# Tp_integrador-Perifericos.net
KiCad netlist of a schematic drawn in Altium Designer
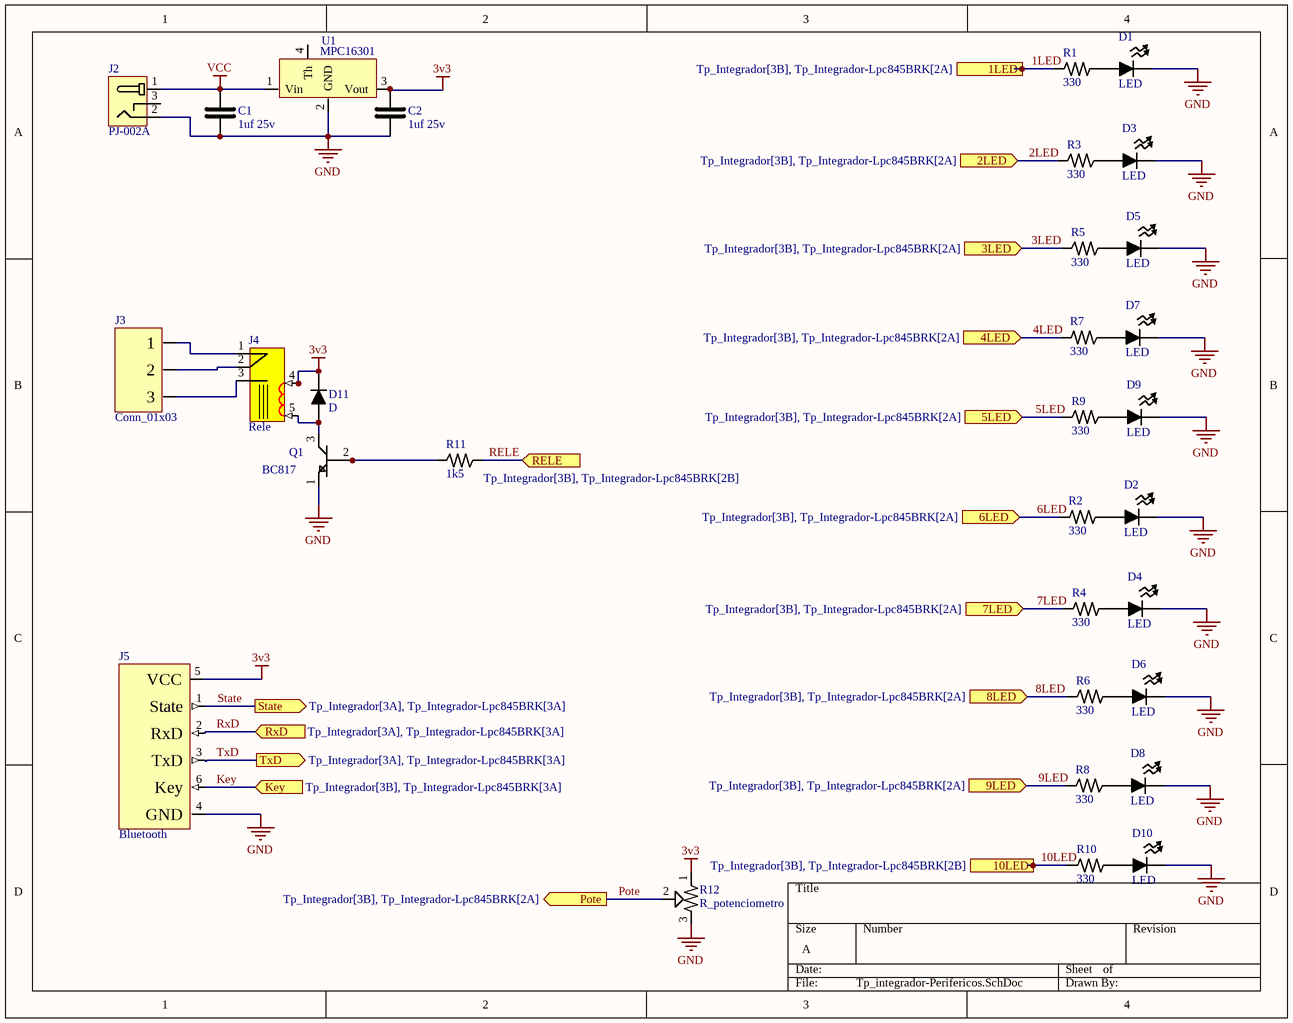
[diagram p0: Tp_integrador-Perifericos.SchDoc]

(export (version "E")
  (design (tool "Eeschema 10.0.6"))
  (components
    (comp (ref "C1")
      (value "1uf 25v")
      (footprint "C_0805")
      (description "Capacitor NP")
      (libsource (lib "Tp_Integrador-SchLib") (part "Capacitor Non Polarized_1"))
    )
    (comp (ref "C2")
      (value "1uf 25v")
      (footprint "C_0805")
      (description "Capacitor NP")
      (libsource (lib "Tp_Integrador-SchLib") (part "Capacitor Non Polarized_1"))
    )
    (comp (ref "D1")
      (value "LED")
      (footprint "LED 5MM")
      (description "Led")
      (libsource (lib "Tp_Integrador-SchLib") (part "LED"))
    )
    (comp (ref "D2")
      (value "LED")
      (footprint "LED 5MM")
      (description "Led")
      (libsource (lib "Tp_Integrador-SchLib") (part "LED"))
    )
    (comp (ref "D3")
      (value "LED")
      (footprint "LED 5MM")
      (description "Led")
      (libsource (lib "Tp_Integrador-SchLib") (part "LED"))
    )
    (comp (ref "D4")
      (value "LED")
      (footprint "LED 5MM")
      (description "Led")
      (libsource (lib "Tp_Integrador-SchLib") (part "LED"))
    )
    (comp (ref "D5")
      (value "LED")
      (footprint "LED 5MM")
      (description "Led")
      (libsource (lib "Tp_Integrador-SchLib") (part "LED"))
    )
    (comp (ref "D6")
      (value "LED")
      (footprint "LED 5MM")
      (description "Led")
      (libsource (lib "Tp_Integrador-SchLib") (part "LED"))
    )
    (comp (ref "D7")
      (value "LED")
      (footprint "LED 5MM")
      (description "Led")
      (libsource (lib "Tp_Integrador-SchLib") (part "LED"))
    )
    (comp (ref "D8")
      (value "LED")
      (footprint "LED 5MM")
      (description "Led")
      (libsource (lib "Tp_Integrador-SchLib") (part "LED"))
    )
    (comp (ref "D9")
      (value "LED")
      (footprint "LED 5MM")
      (description "Led")
      (libsource (lib "Tp_Integrador-SchLib") (part "LED"))
    )
    (comp (ref "D10")
      (value "LED")
      (footprint "LED 5MM")
      (description "Led")
      (libsource (lib "Tp_Integrador-SchLib") (part "LED"))
    )
    (comp (ref "D11")
      (value "D")
      (footprint "Diode")
      (description "DIODO")
      (libsource (lib "Tp_Integrador-SchLib") (part "D"))
    )
    (comp (ref "J2")
      (value "PJ-002A")
      (footprint "Jack")
      (libsource (lib "Tp_Integrador-SchLib") (part "PJ-002A"))
    )
    (comp (ref "J3")
      (value "Conn_01x03")
      (footprint "Bornier")
      (description "Header 3x1")
      (libsource (lib "Tp_Integrador-SchLib") (part "Conn_01x03"))
    )
    (comp (ref "J4") (value "Rele") (footprint "rele") (libsource (lib "Tp_Integrador-SchLib") (part "Rele")))
    (comp (ref "J5")
      (value "Bluetooth")
      (footprint "Hc-05")
      (description "Header 6x1")
      (libsource (lib "Tp_Integrador-SchLib") (part "Bluetooth"))
    )
    (comp (ref "Q1")
      (value "BC817")
      (footprint "Transistor")
      (description "Transistor NPN")
      (libsource (lib "Tp_Integrador-SchLib") (part "Transistor NPN"))
    )
    (comp (ref "R1")
      (value "330")
      (footprint "R_0805")
      (description "Resistor")
      (libsource (lib "Tp_Integrador-SchLib") (part "Resistor"))
    )
    (comp (ref "R2")
      (value "330")
      (footprint "R_0805")
      (description "Resistor")
      (libsource (lib "Tp_Integrador-SchLib") (part "Resistor"))
    )
    (comp (ref "R3")
      (value "330")
      (footprint "R_0805")
      (description "Resistor")
      (libsource (lib "Tp_Integrador-SchLib") (part "Resistor"))
    )
    (comp (ref "R4")
      (value "330")
      (footprint "R_0805")
      (description "Resistor")
      (libsource (lib "Tp_Integrador-SchLib") (part "Resistor"))
    )
    (comp (ref "R5")
      (value "330")
      (footprint "R_0805")
      (description "Resistor")
      (libsource (lib "Tp_Integrador-SchLib") (part "Resistor"))
    )
    (comp (ref "R6")
      (value "330")
      (footprint "R_0805")
      (description "Resistor")
      (libsource (lib "Tp_Integrador-SchLib") (part "Resistor"))
    )
    (comp (ref "R7")
      (value "330")
      (footprint "R_0805")
      (description "Resistor")
      (libsource (lib "Tp_Integrador-SchLib") (part "Resistor"))
    )
    (comp (ref "R8")
      (value "330")
      (footprint "R_0805")
      (description "Resistor")
      (libsource (lib "Tp_Integrador-SchLib") (part "Resistor"))
    )
    (comp (ref "R9")
      (value "330")
      (footprint "R_0805")
      (description "Resistor")
      (libsource (lib "Tp_Integrador-SchLib") (part "Resistor"))
    )
    (comp (ref "R10")
      (value "330")
      (footprint "R_0805")
      (description "Resistor")
      (libsource (lib "Tp_Integrador-SchLib") (part "Resistor"))
    )
    (comp (ref "R11")
      (value "1k5")
      (footprint "R_0805")
      (description "Resistor")
      (libsource (lib "Tp_Integrador-SchLib") (part "Resistor"))
    )
    (comp (ref "R12")
      (value "R_potenciometro")
      (footprint "POTE_9.5MM_PTV09-horizontal")
      (libsource (lib "Tp_Integrador-SchLib") (part "R_potenciometro"))
    )
    (comp (ref "U1")
      (value "MPC16301")
      (footprint "Regulador")
      (description "Regulador Lineal")
      (libsource (lib "Tp_Integrador-SchLib") (part "MPC16301"))
    )
  )
  (nets
    (net (code "1") (name "/1LED") (class "Default")
      (node (ref "R1") (pin "2") (pinfunction "2_2") (pintype "passive"))
    )
    (net (code "2") (name "/2LED") (class "Default")
      (node (ref "R3") (pin "2") (pinfunction "2_2") (pintype "passive"))
    )
    (net (code "3") (name "/3LED") (class "Default")
      (node (ref "R5") (pin "2") (pinfunction "2_2") (pintype "passive"))
    )
    (net (code "4") (name "/4LED") (class "Default")
      (node (ref "R7") (pin "2") (pinfunction "2_2") (pintype "passive"))
    )
    (net (code "5") (name "/5LED") (class "Default")
      (node (ref "R9") (pin "2") (pinfunction "2_2") (pintype "passive"))
    )
    (net (code "6") (name "/6LED") (class "Default")
      (node (ref "R2") (pin "2") (pinfunction "2_2") (pintype "passive"))
    )
    (net (code "7") (name "/7LED") (class "Default")
      (node (ref "R4") (pin "2") (pinfunction "2_2") (pintype "passive"))
    )
    (net (code "8") (name "/8LED") (class "Default")
      (node (ref "R6") (pin "2") (pinfunction "2_2") (pintype "passive"))
    )
    (net (code "9") (name "/9LED") (class "Default")
      (node (ref "R8") (pin "2") (pinfunction "2_2") (pintype "passive"))
    )
    (net (code "10") (name "/10LED") (class "Default")
      (node (ref "R10") (pin "2") (pinfunction "2_2") (pintype "passive"))
    )
    (net (code "11") (name "/Key") (class "Default")
      (node (ref "J5") (pin "6") (pinfunction "Key_6") (pintype "input"))
    )
    (net (code "12") (name "/Pote") (class "Default")
      (node (ref "R12") (pin "2") (pinfunction "2_2") (pintype "passive"))
    )
    (net (code "13") (name "/RELE") (class "Default")
      (node (ref "R11") (pin "1") (pinfunction "1_1") (pintype "passive"))
    )
    (net (code "14") (name "/RxD") (class "Default")
      (node (ref "J5") (pin "2") (pinfunction "RxD_2") (pintype "input"))
    )
    (net (code "15") (name "/State") (class "Default")
      (node (ref "J5") (pin "1") (pinfunction "State_1") (pintype "output"))
    )
    (net (code "16") (name "/TxD") (class "Default")
      (node (ref "J5") (pin "3") (pinfunction "TxD_3") (pintype "output"))
    )
    (net (code "17") (name "3v3") (class "Default")
      (node (ref "C2") (pin "1") (pinfunction "1_1") (pintype "passive"))
      (node (ref "D11") (pin "2") (pinfunction "K_2") (pintype "passive"))
      (node (ref "J4") (pin "4") (pinfunction "4_4") (pintype "input"))
      (node (ref "J5") (pin "5") (pinfunction "VCC_5") (pintype "power_in"))
      (node (ref "R12") (pin "1") (pinfunction "1_1") (pintype "passive"))
      (node (ref "U1") (pin "3") (pinfunction "Vout_3") (pintype "passive"))
    )
    (net (code "18") (name "GND") (class "Default")
      (node (ref "C1") (pin "2") (pinfunction "2_2") (pintype "passive"))
      (node (ref "C2") (pin "2") (pinfunction "2_2") (pintype "passive"))
      (node (ref "D1") (pin "2") (pinfunction "K_2") (pintype "passive"))
      (node (ref "D10") (pin "2") (pinfunction "K_2") (pintype "passive"))
      (node (ref "D2") (pin "2") (pinfunction "K_2") (pintype "passive"))
      (node (ref "D3") (pin "2") (pinfunction "K_2") (pintype "passive"))
      (node (ref "D4") (pin "2") (pinfunction "K_2") (pintype "passive"))
      (node (ref "D5") (pin "2") (pinfunction "K_2") (pintype "passive"))
      (node (ref "D6") (pin "2") (pinfunction "K_2") (pintype "passive"))
      (node (ref "D7") (pin "2") (pinfunction "K_2") (pintype "passive"))
      (node (ref "D8") (pin "2") (pinfunction "K_2") (pintype "passive"))
      (node (ref "D9") (pin "2") (pinfunction "K_2") (pintype "passive"))
      (node (ref "J2") (pin "2") (pinfunction "2_2") (pintype "passive"))
      (node (ref "J5") (pin "4") (pinfunction "GND_4") (pintype "power_in"))
      (node (ref "Q1") (pin "1") (pinfunction "1_1") (pintype "passive"))
      (node (ref "R12") (pin "3") (pinfunction "3_3") (pintype "passive"))
      (node (ref "U1") (pin "2") (pinfunction "GND_2") (pintype "passive"))
    )
    (net (code "19") (name "Net-(D1-A)") (class "Default")
      (node (ref "D1") (pin "1") (pinfunction "A_1") (pintype "passive"))
      (node (ref "R1") (pin "1") (pinfunction "1_1") (pintype "passive"))
    )
    (net (code "20") (name "Net-(D2-A)") (class "Default")
      (node (ref "D2") (pin "1") (pinfunction "A_1") (pintype "passive"))
      (node (ref "R2") (pin "1") (pinfunction "1_1") (pintype "passive"))
    )
    (net (code "21") (name "Net-(D3-A)") (class "Default")
      (node (ref "D3") (pin "1") (pinfunction "A_1") (pintype "passive"))
      (node (ref "R3") (pin "1") (pinfunction "1_1") (pintype "passive"))
    )
    (net (code "22") (name "Net-(D4-A)") (class "Default")
      (node (ref "D4") (pin "1") (pinfunction "A_1") (pintype "passive"))
      (node (ref "R4") (pin "1") (pinfunction "1_1") (pintype "passive"))
    )
    (net (code "23") (name "Net-(D5-A)") (class "Default")
      (node (ref "D5") (pin "1") (pinfunction "A_1") (pintype "passive"))
      (node (ref "R5") (pin "1") (pinfunction "1_1") (pintype "passive"))
    )
    (net (code "24") (name "Net-(D6-A)") (class "Default")
      (node (ref "D6") (pin "1") (pinfunction "A_1") (pintype "passive"))
      (node (ref "R6") (pin "1") (pinfunction "1_1") (pintype "passive"))
    )
    (net (code "25") (name "Net-(D7-A)") (class "Default")
      (node (ref "D7") (pin "1") (pinfunction "A_1") (pintype "passive"))
      (node (ref "R7") (pin "1") (pinfunction "1_1") (pintype "passive"))
    )
    (net (code "26") (name "Net-(D8-A)") (class "Default")
      (node (ref "D8") (pin "1") (pinfunction "A_1") (pintype "passive"))
      (node (ref "R8") (pin "1") (pinfunction "1_1") (pintype "passive"))
    )
    (net (code "27") (name "Net-(D9-A)") (class "Default")
      (node (ref "D9") (pin "1") (pinfunction "A_1") (pintype "passive"))
      (node (ref "R9") (pin "1") (pinfunction "1_1") (pintype "passive"))
    )
    (net (code "28") (name "Net-(D10-A)") (class "Default")
      (node (ref "D10") (pin "1") (pinfunction "A_1") (pintype "passive"))
      (node (ref "R10") (pin "1") (pinfunction "1_1") (pintype "passive"))
    )
    (net (code "29") (name "Net-(D11-A)") (class "Default")
      (node (ref "D11") (pin "1") (pinfunction "A_1") (pintype "passive"))
      (node (ref "J4") (pin "5") (pinfunction "5_5") (pintype "input"))
      (node (ref "Q1") (pin "3") (pinfunction "3_3") (pintype "passive"))
    )
    (net (code "30") (name "Net-(J3-Pad1)") (class "Default")
      (node (ref "J3") (pin "1") (pinfunction "1_1") (pintype "passive"))
      (node (ref "J4") (pin "1") (pinfunction "1_1") (pintype "passive"))
    )
    (net (code "31") (name "Net-(J3-Pad2)") (class "Default")
      (node (ref "J3") (pin "2") (pinfunction "2_2") (pintype "passive"))
      (node (ref "J4") (pin "2") (pinfunction "2_2") (pintype "passive"))
    )
    (net (code "32") (name "Net-(J3-Pad3)") (class "Default")
      (node (ref "J3") (pin "3") (pinfunction "3_3") (pintype "passive"))
      (node (ref "J4") (pin "3") (pinfunction "3_3") (pintype "passive"))
    )
    (net (code "33") (name "Net-(Q1-Pad2)") (class "Default")
      (node (ref "Q1") (pin "2") (pinfunction "2_2") (pintype "passive"))
      (node (ref "R11") (pin "2") (pinfunction "2_2") (pintype "passive"))
    )
    (net (code "34") (name "VCC") (class "Default")
      (node (ref "C1") (pin "1") (pinfunction "1_1") (pintype "passive"))
      (node (ref "J2") (pin "1") (pinfunction "1_1") (pintype "power_in"))
      (node (ref "U1") (pin "1") (pinfunction "Vin_1") (pintype "passive"))
    )
    (net (code "35") (name "unconnected-(J2-Pad3)") (class "Default")
      (node (ref "J2") (pin "3") (pinfunction "3_3") (pintype "power_in"))
    )
    (net (code "36") (name "unconnected-(U1-Th-Pad4)") (class "Default")
      (node (ref "U1") (pin "4") (pinfunction "Th_4") (pintype "passive"))
    )
  )
)
